# ARM-OB.net
KiCad netlist of a schematic drawn in EAGLE
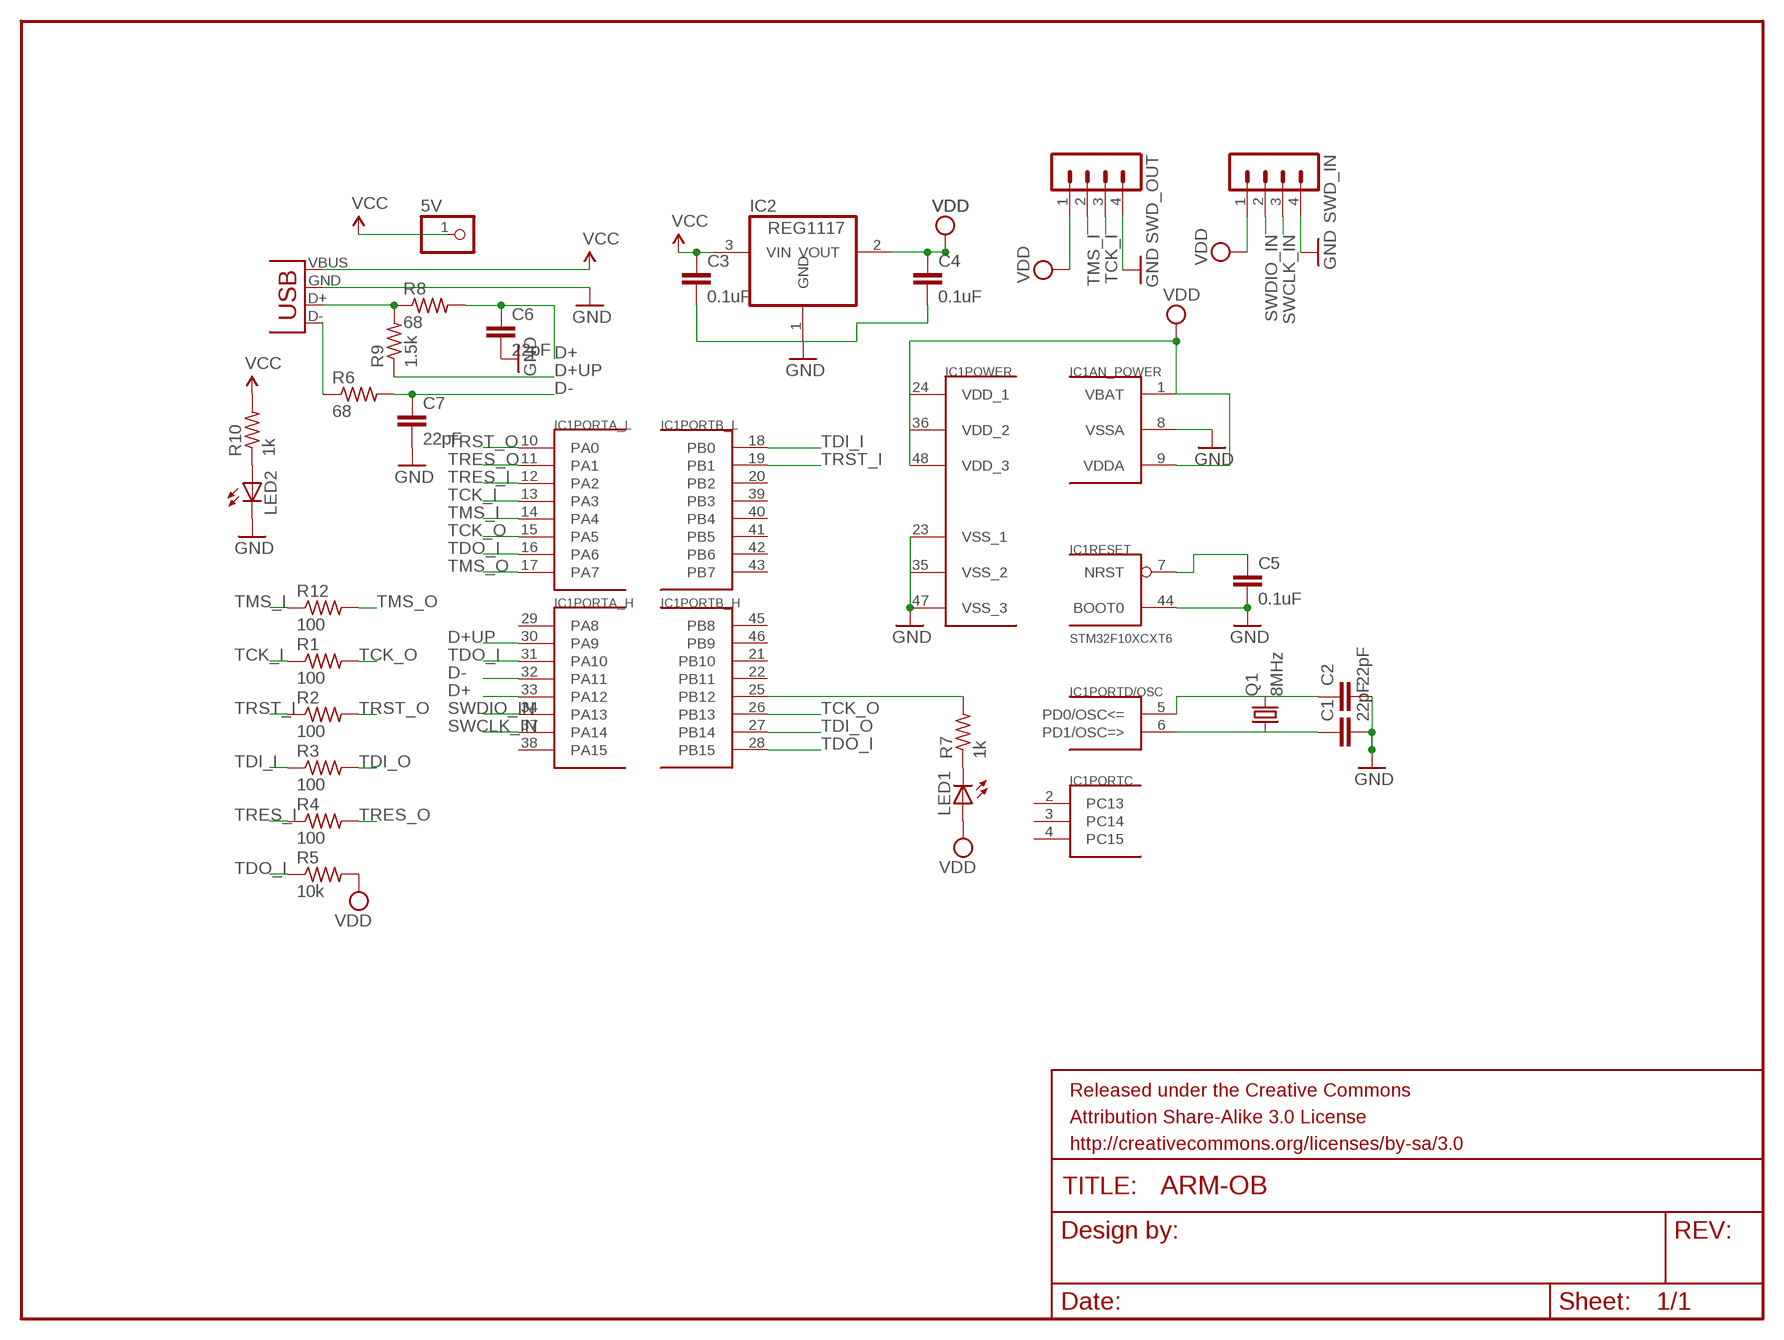
[diagram p0: schematic, sheet 1]

(export (version "E")
  (design (tool "Eeschema 10.0.6"))
  (components
    (comp (ref "5V")
      (value "PINHD-1X1")
      (footprint "eagle-import:1X01")
      (libsource (lib "eagle-import") (part "PINHD-1X1"))
    )
    (comp (ref "C1")
      (value "22pF")
      (footprint "eagle-import:C050-025X075")
      (libsource (lib "eagle-import") (part "C-EU050-025X075"))
    )
    (comp (ref "C2")
      (value "22pF")
      (footprint "eagle-import:C050-025X075")
      (libsource (lib "eagle-import") (part "C-EU050-025X075"))
    )
    (comp (ref "C3")
      (value "0.1uF")
      (footprint "eagle-import:C050-025X075")
      (libsource (lib "eagle-import") (part "C-EU050-025X075"))
    )
    (comp (ref "C4")
      (value "0.1uF")
      (footprint "eagle-import:C050-025X075")
      (libsource (lib "eagle-import") (part "C-EU050-025X075"))
    )
    (comp (ref "C5")
      (value "0.1uF")
      (footprint "eagle-import:C050-025X075")
      (libsource (lib "eagle-import") (part "C-EU050-025X075"))
    )
    (comp (ref "C6")
      (value "22pF")
      (footprint "eagle-import:C050-025X075")
      (libsource (lib "eagle-import") (part "C-EU050-025X075"))
    )
    (comp (ref "C7")
      (value "22pF")
      (footprint "eagle-import:C050-025X075")
      (libsource (lib "eagle-import") (part "C-EU050-025X075"))
    )
    (comp (ref "FRAME1")
      (value "FRAME-LETTER")
      (footprint "eagle-import:CREATIVE_COMMONS")
      (libsource (lib "eagle-import") (part "FRAME-LETTER"))
    )
    (comp (ref "IC1")
      (value "STM32F10XCXT6")
      (footprint "eagle-import:TQFP48")
      (libsource (lib "eagle-import") (part "STM32F10XCXT6"))
    )
    (comp (ref "IC2")
      (value "REG1117")
      (footprint "eagle-import:SOT223")
      (libsource (lib "eagle-import") (part "REG1117"))
    )
    (comp (ref "LED1")
      (value "LEDSML0805")
      (footprint "eagle-import:SML0805")
      (libsource (lib "eagle-import") (part "LEDSML0805"))
    )
    (comp (ref "LED2")
      (value "LEDSML0805")
      (footprint "eagle-import:SML0805")
      (libsource (lib "eagle-import") (part "LEDSML0805"))
    )
    (comp (ref "Q1")
      (value "8MHz")
      (footprint "eagle-import:HC49UP")
      (libsource (lib "eagle-import") (part "CRYSTALHC49UP"))
    )
    (comp (ref "R1")
      (value "100")
      (footprint "eagle-import:0204_7")
      (libsource (lib "eagle-import") (part "R-US_0204/7"))
    )
    (comp (ref "R2")
      (value "100")
      (footprint "eagle-import:0204_7")
      (libsource (lib "eagle-import") (part "R-US_0204/7"))
    )
    (comp (ref "R3")
      (value "100")
      (footprint "eagle-import:0204_7")
      (libsource (lib "eagle-import") (part "R-US_0204/7"))
    )
    (comp (ref "R4")
      (value "100")
      (footprint "eagle-import:0204_7")
      (libsource (lib "eagle-import") (part "R-US_0204/7"))
    )
    (comp (ref "R5")
      (value "10k")
      (footprint "eagle-import:0204_7")
      (libsource (lib "eagle-import") (part "R-US_0204/7"))
    )
    (comp (ref "R6")
      (value "68")
      (footprint "eagle-import:0204_7")
      (libsource (lib "eagle-import") (part "R-US_0204/7"))
    )
    (comp (ref "R7")
      (value "1k")
      (footprint "eagle-import:0204_7")
      (libsource (lib "eagle-import") (part "R-US_0204/7"))
    )
    (comp (ref "R8")
      (value "68")
      (footprint "eagle-import:0204_7")
      (libsource (lib "eagle-import") (part "R-US_0204/7"))
    )
    (comp (ref "R9")
      (value "1.5k")
      (footprint "eagle-import:0204_7")
      (libsource (lib "eagle-import") (part "R-US_0204/7"))
    )
    (comp (ref "R10")
      (value "1k")
      (footprint "eagle-import:0204_7")
      (libsource (lib "eagle-import") (part "R-US_0204/7"))
    )
    (comp (ref "R12")
      (value "100")
      (footprint "eagle-import:0204_7")
      (libsource (lib "eagle-import") (part "R-US_0204/7"))
    )
    (comp (ref "SWD_IN")
      (value "MA04-1")
      (footprint "eagle-import:MA04-1")
      (libsource (lib "eagle-import") (part "MA04-1"))
    )
    (comp (ref "SWD_OUT")
      (value "MA04-1")
      (footprint "eagle-import:MA04-1")
      (libsource (lib "eagle-import") (part "MA04-1"))
    )
    (comp (ref "USB")
      (value "USB-A-H")
      (footprint "eagle-import:USB-A-H")
      (libsource (lib "eagle-import") (part "USB-A-H"))
    )
  )
  (nets
    (net (code "1") (name "/D+") (class "Default")
      (node (ref "C6") (pin "1") (pinfunction "1_1") (pintype "passive"))
      (node (ref "IC1") (pin "33") (pinfunction "PA12_33") (pintype "bidirectional"))
      (node (ref "R8") (pin "2") (pinfunction "2_2") (pintype "passive"))
    )
    (net (code "2") (name "/D+UP") (class "Default")
      (node (ref "IC1") (pin "30") (pinfunction "PA9_30") (pintype "bidirectional"))
      (node (ref "R9") (pin "1") (pinfunction "1_1") (pintype "passive"))
    )
    (net (code "3") (name "/D-") (class "Default")
      (node (ref "C7") (pin "1") (pinfunction "1_1") (pintype "passive"))
      (node (ref "IC1") (pin "32") (pinfunction "PA11_32") (pintype "bidirectional"))
      (node (ref "R6") (pin "2") (pinfunction "2_2") (pintype "passive"))
    )
    (net (code "4") (name "/SWCLK_IN") (class "Default")
      (node (ref "IC1") (pin "37") (pinfunction "PA14_37") (pintype "bidirectional"))
      (node (ref "SWD_IN") (pin "3") (pinfunction "3_3") (pintype "passive"))
    )
    (net (code "5") (name "/SWDIO_IN") (class "Default")
      (node (ref "IC1") (pin "34") (pinfunction "PA13_34") (pintype "bidirectional"))
      (node (ref "SWD_IN") (pin "2") (pinfunction "2_2") (pintype "passive"))
    )
    (net (code "6") (name "/TCK_I") (class "Default")
      (node (ref "IC1") (pin "13") (pinfunction "PA3_13") (pintype "bidirectional"))
      (node (ref "R1") (pin "1") (pinfunction "1_1") (pintype "passive"))
      (node (ref "SWD_OUT") (pin "3") (pinfunction "3_3") (pintype "passive"))
    )
    (net (code "7") (name "/TCK_O") (class "Default")
      (node (ref "IC1") (pin "15") (pinfunction "PA5_15") (pintype "bidirectional"))
      (node (ref "IC1") (pin "26") (pinfunction "PB13_26") (pintype "bidirectional"))
      (node (ref "R1") (pin "2") (pinfunction "2_2") (pintype "passive"))
    )
    (net (code "8") (name "/TDI_I") (class "Default")
      (node (ref "IC1") (pin "18") (pinfunction "PB0_18") (pintype "bidirectional"))
      (node (ref "R3") (pin "1") (pinfunction "1_1") (pintype "passive"))
    )
    (net (code "9") (name "/TDI_O") (class "Default")
      (node (ref "IC1") (pin "27") (pinfunction "PB14_27") (pintype "bidirectional"))
      (node (ref "R3") (pin "2") (pinfunction "2_2") (pintype "passive"))
    )
    (net (code "10") (name "/TDO_I") (class "Default")
      (node (ref "IC1") (pin "16") (pinfunction "PA6_16") (pintype "bidirectional"))
      (node (ref "IC1") (pin "28") (pinfunction "PB15_28") (pintype "bidirectional"))
      (node (ref "IC1") (pin "31") (pinfunction "PA10_31") (pintype "bidirectional"))
      (node (ref "R5") (pin "1") (pinfunction "1_1") (pintype "passive"))
    )
    (net (code "11") (name "/TMS_I") (class "Default")
      (node (ref "IC1") (pin "14") (pinfunction "PA4_14") (pintype "bidirectional"))
      (node (ref "R12") (pin "1") (pinfunction "1_1") (pintype "passive"))
      (node (ref "SWD_OUT") (pin "2") (pinfunction "2_2") (pintype "passive"))
    )
    (net (code "12") (name "/TMS_O") (class "Default")
      (node (ref "IC1") (pin "17") (pinfunction "PA7_17") (pintype "bidirectional"))
      (node (ref "R12") (pin "2") (pinfunction "2_2") (pintype "passive"))
    )
    (net (code "13") (name "/TRES_I") (class "Default")
      (node (ref "IC1") (pin "12") (pinfunction "PA2_12") (pintype "bidirectional"))
      (node (ref "R4") (pin "1") (pinfunction "1_1") (pintype "passive"))
    )
    (net (code "14") (name "/TRES_O") (class "Default")
      (node (ref "IC1") (pin "11") (pinfunction "PA1_11") (pintype "bidirectional"))
      (node (ref "R4") (pin "2") (pinfunction "2_2") (pintype "passive"))
    )
    (net (code "15") (name "/TRST_I") (class "Default")
      (node (ref "IC1") (pin "19") (pinfunction "PB1_19") (pintype "bidirectional"))
      (node (ref "R2") (pin "1") (pinfunction "1_1") (pintype "passive"))
    )
    (net (code "16") (name "/TRST_O") (class "Default")
      (node (ref "IC1") (pin "10") (pinfunction "PA0_10") (pintype "bidirectional"))
      (node (ref "R2") (pin "2") (pinfunction "2_2") (pintype "passive"))
    )
    (net (code "17") (name "GND") (class "Default")
      (node (ref "C1") (pin "2") (pinfunction "2_2") (pintype "passive"))
      (node (ref "C2") (pin "2") (pinfunction "2_2") (pintype "passive"))
      (node (ref "C3") (pin "2") (pinfunction "2_2") (pintype "passive"))
      (node (ref "C4") (pin "2") (pinfunction "2_2") (pintype "passive"))
      (node (ref "C5") (pin "2") (pinfunction "2_2") (pintype "passive"))
      (node (ref "C6") (pin "2") (pinfunction "2_2") (pintype "passive"))
      (node (ref "C7") (pin "2") (pinfunction "2_2") (pintype "passive"))
      (node (ref "IC1") (pin "23") (pinfunction "VSS_1_23") (pintype "power_in"))
      (node (ref "IC1") (pin "35") (pinfunction "VSS_2_35") (pintype "power_in"))
      (node (ref "IC1") (pin "44") (pinfunction "BOOT0_44") (pintype "input"))
      (node (ref "IC1") (pin "47") (pinfunction "VSS_3_47") (pintype "power_in"))
      (node (ref "IC1") (pin "8") (pinfunction "VSSA_8") (pintype "power_in"))
      (node (ref "IC2") (pin "1") (pinfunction "GND_1") (pintype "power_in"))
      (node (ref "LED2") (pin "C") (pinfunction "C_C") (pintype "passive"))
      (node (ref "SWD_IN") (pin "4") (pinfunction "4_4") (pintype "passive"))
      (node (ref "SWD_OUT") (pin "4") (pinfunction "4_4") (pintype "passive"))
      (node (ref "USB") (pin "GND") (pinfunction "VBUS_GND") (pintype "bidirectional"))
    )
    (net (code "18") (name "Net-(IC1D-PB12)") (class "Default")
      (node (ref "IC1") (pin "25") (pinfunction "PB12_25") (pintype "bidirectional"))
      (node (ref "R7") (pin "2") (pinfunction "2_2") (pintype "passive"))
    )
    (net (code "19") (name "Net-(IC1G-PD0{slash}OSC<=)") (class "Default")
      (node (ref "C2") (pin "1") (pinfunction "1_1") (pintype "passive"))
      (node (ref "IC1") (pin "5") (pinfunction "PD0/OSC<=_5") (pintype "bidirectional"))
      (node (ref "Q1") (pin "2") (pinfunction "2_2") (pintype "passive"))
    )
    (net (code "20") (name "Net-(IC1G-PD1{slash}OSC=>)") (class "Default")
      (node (ref "C1") (pin "1") (pinfunction "1_1") (pintype "passive"))
      (node (ref "IC1") (pin "6") (pinfunction "PD1/OSC=>_6") (pintype "bidirectional"))
      (node (ref "Q1") (pin "1") (pinfunction "1_1") (pintype "passive"))
    )
    (net (code "21") (name "Net-(IC1I-NRST)") (class "Default")
      (node (ref "C5") (pin "1") (pinfunction "1_1") (pintype "passive"))
      (node (ref "IC1") (pin "7") (pinfunction "NRST_7") (pintype "input"))
    )
    (net (code "22") (name "Net-(LED1-PadC)") (class "Default")
      (node (ref "LED1") (pin "C") (pinfunction "C_C") (pintype "passive"))
      (node (ref "R7") (pin "1") (pinfunction "1_1") (pintype "passive"))
    )
    (net (code "23") (name "Net-(LED2-PadA)") (class "Default")
      (node (ref "LED2") (pin "A") (pinfunction "A_A") (pintype "passive"))
      (node (ref "R10") (pin "1") (pinfunction "1_1") (pintype "passive"))
    )
    (net (code "24") (name "Net-(USB-D+)") (class "Default")
      (node (ref "R6") (pin "1") (pinfunction "1_1") (pintype "passive"))
      (node (ref "USB") (pin "D-") (pinfunction "D+_D-") (pintype "bidirectional"))
    )
    (net (code "25") (name "Net-(USB-D-)") (class "Default")
      (node (ref "R8") (pin "1") (pinfunction "1_1") (pintype "passive"))
      (node (ref "R9") (pin "2") (pinfunction "2_2") (pintype "passive"))
      (node (ref "USB") (pin "D+") (pinfunction "D-_D+") (pintype "bidirectional"))
    )
    (net (code "26") (name "VCC") (class "Default")
      (node (ref "5V") (pin "1") (pinfunction "1_1") (pintype "passive"))
      (node (ref "C3") (pin "1") (pinfunction "1_1") (pintype "passive"))
      (node (ref "IC2") (pin "3") (pinfunction "VIN_3") (pintype "input"))
      (node (ref "R10") (pin "2") (pinfunction "2_2") (pintype "passive"))
      (node (ref "USB") (pin "VBUS") (pinfunction "GND_VBUS") (pintype "bidirectional"))
    )
    (net (code "27") (name "VDD") (class "Default")
      (node (ref "C4") (pin "1") (pinfunction "1_1") (pintype "passive"))
      (node (ref "IC1") (pin "1") (pinfunction "VBAT_1") (pintype "power_in"))
      (node (ref "IC1") (pin "24") (pinfunction "VDD_1_24") (pintype "power_in"))
      (node (ref "IC1") (pin "36") (pinfunction "VDD_2_36") (pintype "power_in"))
      (node (ref "IC1") (pin "48") (pinfunction "VDD_3_48") (pintype "power_in"))
      (node (ref "IC1") (pin "9") (pinfunction "VDDA_9") (pintype "power_in"))
      (node (ref "IC2") (pin "2") (pinfunction "VOUT_2") (pintype "output"))
      (node (ref "LED1") (pin "A") (pinfunction "A_A") (pintype "passive"))
      (node (ref "R5") (pin "2") (pinfunction "2_2") (pintype "passive"))
      (node (ref "SWD_IN") (pin "1") (pinfunction "1_1") (pintype "passive"))
      (node (ref "SWD_OUT") (pin "1") (pinfunction "1_1") (pintype "passive"))
    )
    (net (code "28") (name "unconnected-(IC1B-PA8-Pad29)") (class "Default")
      (node (ref "IC1") (pin "29") (pinfunction "PA8_29") (pintype "bidirectional"))
    )
    (net (code "29") (name "unconnected-(IC1B-PA15-Pad38)") (class "Default")
      (node (ref "IC1") (pin "38") (pinfunction "PA15_38") (pintype "bidirectional"))
    )
    (net (code "30") (name "unconnected-(IC1D-PB8-Pad45)") (class "Default")
      (node (ref "IC1") (pin "45") (pinfunction "PB8_45") (pintype "bidirectional"))
    )
    (net (code "31") (name "unconnected-(IC1D-PB9-Pad46)") (class "Default")
      (node (ref "IC1") (pin "46") (pinfunction "PB9_46") (pintype "bidirectional"))
    )
    (net (code "32") (name "unconnected-(IC1D-PB10-Pad21)") (class "Default")
      (node (ref "IC1") (pin "21") (pinfunction "PB10_21") (pintype "bidirectional"))
    )
    (net (code "33") (name "unconnected-(IC1D-PB11-Pad22)") (class "Default")
      (node (ref "IC1") (pin "22") (pinfunction "PB11_22") (pintype "bidirectional"))
    )
    (net (code "34") (name "unconnected-(IC1E-PB2-Pad20)") (class "Default")
      (node (ref "IC1") (pin "20") (pinfunction "PB2_20") (pintype "bidirectional"))
    )
    (net (code "35") (name "unconnected-(IC1E-PB3-Pad39)") (class "Default")
      (node (ref "IC1") (pin "39") (pinfunction "PB3_39") (pintype "bidirectional"))
    )
    (net (code "36") (name "unconnected-(IC1E-PB4-Pad40)") (class "Default")
      (node (ref "IC1") (pin "40") (pinfunction "PB4_40") (pintype "bidirectional"))
    )
    (net (code "37") (name "unconnected-(IC1E-PB5-Pad41)") (class "Default")
      (node (ref "IC1") (pin "41") (pinfunction "PB5_41") (pintype "bidirectional"))
    )
    (net (code "38") (name "unconnected-(IC1E-PB6-Pad42)") (class "Default")
      (node (ref "IC1") (pin "42") (pinfunction "PB6_42") (pintype "bidirectional"))
    )
    (net (code "39") (name "unconnected-(IC1E-PB7-Pad43)") (class "Default")
      (node (ref "IC1") (pin "43") (pinfunction "PB7_43") (pintype "bidirectional"))
    )
    (net (code "40") (name "unconnected-(IC1F-PC13-Pad2)") (class "Default")
      (node (ref "IC1") (pin "2") (pinfunction "PC13_2") (pintype "bidirectional"))
    )
    (net (code "41") (name "unconnected-(IC1F-PC14-Pad3)") (class "Default")
      (node (ref "IC1") (pin "3") (pinfunction "PC14_3") (pintype "bidirectional"))
    )
    (net (code "42") (name "unconnected-(IC1F-PC15-Pad4)") (class "Default")
      (node (ref "IC1") (pin "4") (pinfunction "PC15_4") (pintype "bidirectional"))
    )
  )
)
